# CH32V205V-R0.net
KiCad netlist of a schematic drawn in Altium Designer
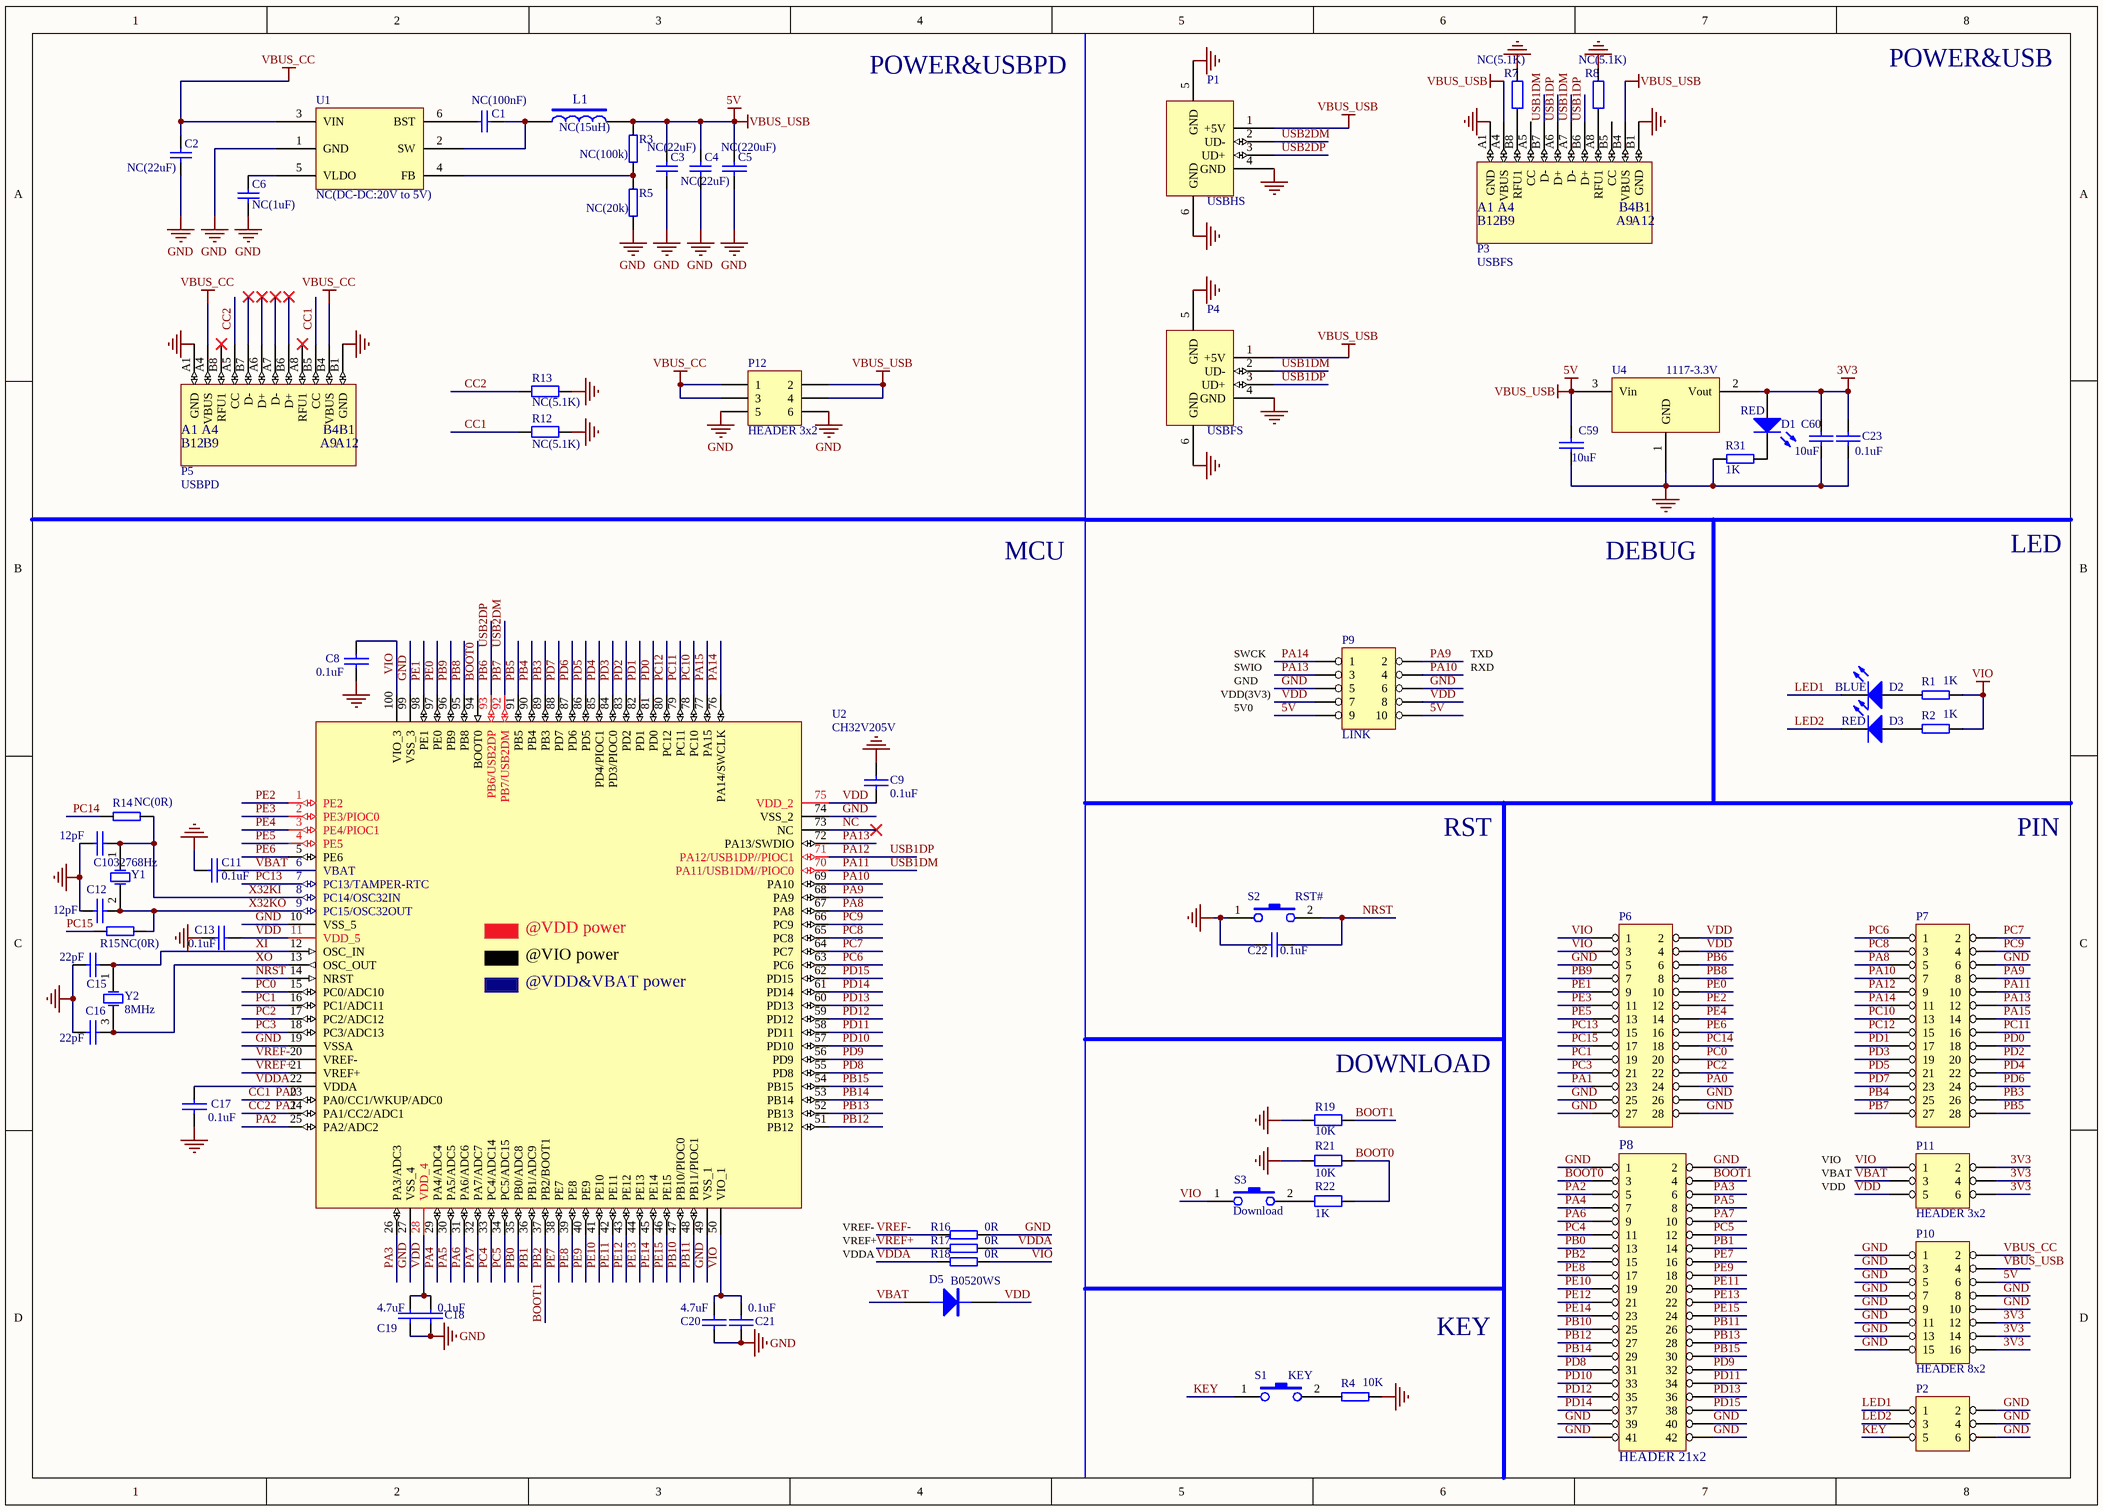
[diagram p0: CH32V205V-R0.SchDoc]

(export (version "E")
  (design (tool "Eeschema 10.0.6"))
  (components
    (comp (ref "C1")
      (value "NC(100nF)")
      (footprint "0402_C")
      (description "贴片电容")
      (libsource (lib "Miscellaneous Devices LC") (part "0603 100nF (104) 10% 50V"))
    )
    (comp (ref "C2")
      (value "NC(22uF)")
      (footprint "0805_C")
      (description "贴片电容")
      (libsource (lib "Miscellaneous Devices LC") (part "0603 100nF (104) 10% 50V"))
    )
    (comp (ref "C3")
      (value "NC(22uF)")
      (footprint "0805_C")
      (description "贴片电容")
      (libsource (lib "Miscellaneous Devices LC") (part "0603 100nF (104) 10% 50V"))
    )
    (comp (ref "C4")
      (value "NC(22uF)")
      (footprint "0805_C")
      (description "贴片电容")
      (libsource (lib "Miscellaneous Devices LC") (part "0603 100nF (104) 10% 50V"))
    )
    (comp (ref "C5")
      (value "NC(220uF)")
      (footprint "CD0.1")
      (description "Capacitor")
      (libsource (lib "") (part "CAP_2"))
    )
    (comp (ref "C6")
      (value "NC(1uF)")
      (footprint "0402_C")
      (description "贴片电容")
      (libsource (lib "Miscellaneous Devices LC") (part "0603 100nF (104) 10% 50V"))
    )
    (comp (ref "C8")
      (value "0.1uF")
      (footprint "0603_C")
      (description "Capacitor")
      (libsource (lib "*") (part "CAP"))
    )
    (comp (ref "C9")
      (value "0.1uF")
      (footprint "0603_C")
      (description "Capacitor")
      (libsource (lib "*") (part "CAP"))
    )
    (comp (ref "C10")
      (value "12pF")
      (footprint "0603_C")
      (description "Capacitor")
      (libsource (lib "*") (part "CAP"))
    )
    (comp (ref "C11")
      (value "0.1uF")
      (footprint "0603_C")
      (description "Capacitor")
      (libsource (lib "*") (part "CAP"))
    )
    (comp (ref "C12")
      (value "12pF")
      (footprint "0603_C")
      (description "Capacitor")
      (libsource (lib "*") (part "CAP"))
    )
    (comp (ref "C13")
      (value "0.1uF")
      (footprint "0603_C")
      (description "Capacitor")
      (libsource (lib "*") (part "CAP"))
    )
    (comp (ref "C15")
      (value "22pF")
      (footprint "0603_C")
      (description "Capacitor")
      (libsource (lib "*") (part "CAP"))
    )
    (comp (ref "C16")
      (value "22pF")
      (footprint "0603_C")
      (description "Capacitor")
      (libsource (lib "*") (part "CAP"))
    )
    (comp (ref "C17")
      (value "0.1uF")
      (footprint "0603_C")
      (description "Capacitor")
      (libsource (lib "*") (part "CAP"))
    )
    (comp (ref "C18")
      (value "0.1uF")
      (footprint "0603_C")
      (description "Capacitor")
      (libsource (lib "*") (part "CAP"))
    )
    (comp (ref "C19")
      (value "4.7uF")
      (footprint "0603_C")
      (description "Capacitor")
      (libsource (lib "*") (part "CAP"))
    )
    (comp (ref "C20")
      (value "4.7uF")
      (footprint "0603_C")
      (description "Capacitor")
      (libsource (lib "*") (part "CAP"))
    )
    (comp (ref "C21")
      (value "0.1uF")
      (footprint "0603_C")
      (description "Capacitor")
      (libsource (lib "*") (part "CAP"))
    )
    (comp (ref "C22")
      (value "0.1uF")
      (footprint "0603_C")
      (description "Capacitor")
      (libsource (lib "") (part "CAP_1"))
    )
    (comp (ref "C23")
      (value "0.1uF")
      (footprint "0402_C")
      (description "Capacitor")
      (libsource (lib "*") (part "CAP"))
    )
    (comp (ref "C59")
      (value "10uF")
      (footprint "0603_C")
      (description "Capacitor")
      (libsource (lib "*") (part "CAP"))
    )
    (comp (ref "C60")
      (value "10uF")
      (footprint "0603_C")
      (description "Capacitor")
      (libsource (lib "*") (part "CAP"))
    )
    (comp (ref "D1")
      (value "RED")
      (footprint "0603+")
      (description "Typical INFRARED GaAs LED")
      (fields (field (name "PUBLISHER") "Altium Limited"))
      (libsource (lib "*") (part "LED0"))
    )
    (comp (ref "D2")
      (value "BLUE")
      (footprint "0603+")
      (description "Typical INFRARED GaAs LED")
      (fields (field (name "PUBLISHER") "Altium Limited"))
      (libsource (lib "*") (part "LED0"))
    )
    (comp (ref "D3")
      (value "RED")
      (footprint "0603+")
      (description "Typical INFRARED GaAs LED")
      (fields (field (name "PUBLISHER") "Altium Limited"))
      (libsource (lib "*") (part "LED0"))
    )
    (comp (ref "D5")
      (value "B0520WS")
      (footprint "SOD-323")
      (description "Diode")
      (libsource (lib "*") (part "DIODE"))
    )
    (comp (ref "L1")
      (value "NC(15uH)")
      (footprint "SMD_6x6mm")
      (libsource (lib "wch_sch_others") (part "INDUCTOR"))
    )
    (comp (ref "P1")
      (value "USBHS")
      (footprint "USBAF")
      (description "USB Port")
      (libsource (lib "*") (part "USB"))
    )
    (comp (ref "P2")
      (value "IO")
      (footprint "MYPCB:IDC6-2.54mm")
      (description "Header, 3-Pin, Dual row")
      (libsource (lib "wch_sch_others") (part "HEADER 3x2"))
    )
    (comp (ref "P3")
      (value "USBFS")
      (footprint "TYPE-C-Receptacle-2.0")
      (libsource (lib "*") (part "TYPE-C1"))
    )
    (comp (ref "P4")
      (value "USBFS")
      (footprint "USBAF")
      (description "USB Port")
      (libsource (lib "*") (part "USB"))
    )
    (comp (ref "P5")
      (value "USBPD")
      (footprint "TYPE-C-Receptacle-2.0")
      (libsource (lib "*") (part "TYPE-C1"))
    )
    (comp (ref "P6")
      (value "~")
      (footprint "MYPCB:IDC28-2.54MM")
      (description "Header, 14-Pin, Dual row")
      (libsource (lib "wch_sch_others") (part "HEADER 14x2"))
    )
    (comp (ref "P7")
      (value "~")
      (footprint "MYPCB:IDC28-2.54MM")
      (description "Header, 14-Pin, Dual row")
      (libsource (lib "wch_sch_others") (part "HEADER 14x2"))
    )
    (comp (ref "P8")
      (value "HEADER 21x2")
      (footprint "MYPCB:IDC42-2.54MM")
      (description "Header, 21-Pin, Dual row")
      (libsource (lib "wch_sch_others") (part "HEADER 21x2"))
    )
    (comp (ref "P9")
      (value "LINK")
      (footprint "MYPCB:IDC10-2.54mm")
      (description "Header, 5-Pin, Dual row")
      (libsource (lib "wch_sch_others") (part "HEADER 5x2"))
    )
    (comp (ref "P10")
      (value "HEADER 8x2")
      (footprint "MYPCB:IDC16-2.54mm")
      (description "Header, 8-Pin, Dual row")
      (libsource (lib "wch_sch_others") (part "HEADER 8x2"))
    )
    (comp (ref "P11")
      (value "HEADER 3x2")
      (footprint "MYPCB:IDC6-2.54mm")
      (description "Header, 3-Pin, Dual row")
      (libsource (lib "wch_sch_others") (part "HEADER 3x2"))
    )
    (comp (ref "P12")
      (value "HEADER 3x2")
      (footprint "MYPCB:IDC6-2.54mm")
      (description "Header, 3-Pin, Dual row")
      (libsource (lib "") (part "HEADER 3x2_1"))
    )
    (comp (ref "R1") (value "1K") (footprint "CHXXX:0603") (libsource (lib "wch_sch_others") (part "RES")))
    (comp (ref "R2") (value "1K") (footprint "CHXXX:0603") (libsource (lib "wch_sch_others") (part "RES")))
    (comp (ref "R3") (value "NC(100k)") (footprint "CHXXX:0603") (libsource (lib "") (part "RES_1")))
    (comp (ref "R4") (value "10K") (footprint "CHXXX:0603") (libsource (lib "wch_sch_others") (part "RES")))
    (comp (ref "R5") (value "NC(20k)") (footprint "CHXXX:0603") (libsource (lib "") (part "RES_1")))
    (comp (ref "R7")
      (value "NC(5.1K)")
      (footprint "0603")
      (description "Resistor")
      (libsource (lib "") (part "Res2_2"))
    )
    (comp (ref "R8")
      (value "NC(5.1K)")
      (footprint "0603")
      (description "Resistor")
      (libsource (lib "") (part "Res2_2"))
    )
    (comp (ref "R12")
      (value "NC(5.1K)")
      (footprint "0402")
      (description "Resistor")
      (libsource (lib "") (part "Res2_1"))
    )
    (comp (ref "R13")
      (value "NC(5.1K)")
      (footprint "0402")
      (description "Resistor")
      (libsource (lib "") (part "Res2_1"))
    )
    (comp (ref "R14")
      (value "NC(0R)")
      (footprint "CHXXX:0603")
      (libsource (lib "wch_sch_others") (part "RES"))
    )
    (comp (ref "R15")
      (value "NC(0R)")
      (footprint "CHXXX:0603")
      (libsource (lib "wch_sch_others") (part "RES"))
    )
    (comp (ref "R16") (value "0R") (footprint "CHXXX:0603") (libsource (lib "*") (part "R")))
    (comp (ref "R17") (value "0R") (footprint "CHXXX:0603") (libsource (lib "*") (part "R")))
    (comp (ref "R18") (value "0R") (footprint "CHXXX:0603") (libsource (lib "*") (part "R")))
    (comp (ref "R19")
      (value "10K")
      (footprint "CHXXX:0603")
      (description "Resistor")
      (fields (field (name "PUBLISHER") "Altium Limited"))
      (libsource (lib "Miscellaneous Devices") (part "Res2"))
    )
    (comp (ref "R21")
      (value "10K")
      (footprint "CHXXX:0603")
      (description "Resistor")
      (fields (field (name "PUBLISHER") "Altium Limited"))
      (libsource (lib "Miscellaneous Devices") (part "Res2"))
    )
    (comp (ref "R22")
      (value "1K")
      (footprint "CHXXX:0603")
      (description "Resistor")
      (fields (field (name "PUBLISHER") "Altium Limited"))
      (libsource (lib "Miscellaneous Devices") (part "Res2"))
    )
    (comp (ref "R31") (value "1K") (footprint "0402") (libsource (lib "wch_sch_others") (part "RES")))
    (comp (ref "S1")
      (value "KEY")
      (footprint "SMD_6.1x3.65x2.5mm-KEY")
      (libsource (lib "wch_sch_others") (part "KEY1"))
    )
    (comp (ref "S2")
      (value "RST#")
      (footprint "SMD_6.1x3.65x2.5mm-KEY")
      (libsource (lib "wch_sch_others") (part "KEY1"))
    )
    (comp (ref "S3")
      (value "Download")
      (footprint "SMD_6.1x3.65x2.5mm-KEY")
      (libsource (lib "wch_sch_others") (part "KEY1"))
    )
    (comp (ref "U1")
      (value "NC(DC-DC:20V to 5V)")
      (footprint "SOT-23-6")
      (description "DCDC")
      (libsource (lib "wch_sch_others") (part "TPS54202"))
    )
    (comp (ref "U2")
      (value "CH32V205V")
      (footprint "LQFP100")
      (description "RISC-V MCU, 192MHz, USB_480M, USB FS, PD, PIOC, ADC, TKEY, 2*OPA, 2*CMP")
      (libsource (lib "CHXXX") (part "CH32V205V"))
    )
    (comp (ref "U4")
      (value "1117-3.3V")
      (footprint "SOT-223")
      (libsource (lib "wch_sch_others") (part "1117-3.3V"))
    )
    (comp (ref "Y1")
      (value "32768Hz")
      (footprint "FC-135")
      (description "Crystal Oscillator")
      (fields (field (name "PUBLISHER") "Altium Limited"))
      (libsource (lib "") (part "XTAL_1"))
    )
    (comp (ref "Y2")
      (value "8MHz")
      (footprint "XT3225")
      (description "Crystal Oscillator")
      (fields (field (name "PUBLISHER") "Altium Limited"))
      (libsource (lib "*") (part "XTAL"))
    )
  )
  (nets
    (net (code "2") (name "/BOOT0") (class "Default")
      (node (ref "P8") (pin "3") (pinfunction "3_3") (pintype "passive"))
      (node (ref "R21") (pin "1") (pinfunction "1_1") (pintype "passive"))
      (node (ref "R22") (pin "1") (pinfunction "1_1") (pintype "passive"))
      (node (ref "U2") (pin "94") (pinfunction "BOOT0_94") (pintype "input"))
    )
    (net (code "3") (name "/BOOT1") (class "Default")
      (node (ref "P8") (pin "15") (pinfunction "15_15") (pintype "passive"))
      (node (ref "P8") (pin "4") (pinfunction "4_4") (pintype "passive"))
      (node (ref "R19") (pin "1") (pinfunction "1_1") (pintype "passive"))
      (node (ref "U2") (pin "37") (pinfunction "PB2/BOOT1_37") (pintype "bidirectional"))
    )
    (net (code "4") (name "/CC1") (class "Default")
      (node (ref "P5") (pin "B5") (pinfunction "CC_B5") (pintype "bidirectional"))
      (node (ref "P6") (pin "24") (pinfunction "24_24") (pintype "passive"))
      (node (ref "R12") (pin "1") (pinfunction "1_1") (pintype "passive"))
      (node (ref "U2") (pin "23") (pinfunction "PA0/CC1/WKUP/ADC0_23") (pintype "bidirectional"))
    )
    (net (code "5") (name "/CC2") (class "Default")
      (node (ref "P5") (pin "A5") (pinfunction "CC_A5") (pintype "bidirectional"))
      (node (ref "P6") (pin "23") (pinfunction "23_23") (pintype "passive"))
      (node (ref "R13") (pin "1") (pinfunction "1_1") (pintype "passive"))
      (node (ref "U2") (pin "24") (pinfunction "PA1/CC2/ADC1_24") (pintype "bidirectional"))
    )
    (net (code "6") (name "/KEY") (class "Default")
      (node (ref "P2") (pin "5") (pinfunction "5_5") (pintype "passive"))
      (node (ref "S1") (pin "1") (pinfunction "1_1") (pintype "passive"))
    )
    (net (code "7") (name "/LED1") (class "Default")
      (node (ref "D2") (pin "2") (pinfunction "K_2") (pintype "passive"))
      (node (ref "P2") (pin "1") (pinfunction "1_1") (pintype "passive"))
    )
    (net (code "8") (name "/LED2") (class "Default")
      (node (ref "D3") (pin "2") (pinfunction "K_2") (pintype "passive"))
      (node (ref "P2") (pin "3") (pinfunction "3_3") (pintype "passive"))
    )
    (net (code "9") (name "/NC") (class "Default")
      (node (ref "U2") (pin "73") (pinfunction "NC_73") (pintype "tri_state+no_connect"))
    )
    (net (code "10") (name "/NRST") (class "Default")
      (node (ref "C22") (pin "2") (pinfunction "2_2") (pintype "passive"))
      (node (ref "S2") (pin "2") (pinfunction "2_2") (pintype "passive"))
      (node (ref "U2") (pin "14") (pinfunction "NRST_14") (pintype "input"))
    )
    (net (code "11") (name "/PA2") (class "Default")
      (node (ref "P8") (pin "5") (pinfunction "5_5") (pintype "passive"))
      (node (ref "U2") (pin "25") (pinfunction "PA2/ADC2_25") (pintype "bidirectional"))
    )
    (net (code "12") (name "/PA3") (class "Default")
      (node (ref "P8") (pin "6") (pinfunction "6_6") (pintype "passive"))
      (node (ref "U2") (pin "26") (pinfunction "PA3/ADC3_26") (pintype "bidirectional"))
    )
    (net (code "13") (name "/PA4") (class "Default")
      (node (ref "P8") (pin "7") (pinfunction "7_7") (pintype "passive"))
      (node (ref "U2") (pin "29") (pinfunction "PA4/ADC4_29") (pintype "bidirectional"))
    )
    (net (code "14") (name "/PA5") (class "Default")
      (node (ref "P8") (pin "8") (pinfunction "8_8") (pintype "passive"))
      (node (ref "U2") (pin "30") (pinfunction "PA5/ADC5_30") (pintype "bidirectional"))
    )
    (net (code "15") (name "/PA6") (class "Default")
      (node (ref "P8") (pin "9") (pinfunction "9_9") (pintype "passive"))
      (node (ref "U2") (pin "31") (pinfunction "PA6/ADC6_31") (pintype "bidirectional"))
    )
    (net (code "16") (name "/PA7") (class "Default")
      (node (ref "P8") (pin "10") (pinfunction "10_10") (pintype "passive"))
      (node (ref "U2") (pin "32") (pinfunction "PA7/ADC7_32") (pintype "bidirectional"))
    )
    (net (code "17") (name "/PA8") (class "Default")
      (node (ref "P7") (pin "5") (pinfunction "5_5") (pintype "passive"))
      (node (ref "U2") (pin "67") (pinfunction "PA8_67") (pintype "bidirectional"))
    )
    (net (code "18") (name "/PA9") (class "Default")
      (node (ref "P7") (pin "8") (pinfunction "8_8") (pintype "passive"))
      (node (ref "P9") (pin "2") (pinfunction "2_2") (pintype "passive"))
      (node (ref "U2") (pin "68") (pinfunction "PA9_68") (pintype "bidirectional"))
    )
    (net (code "19") (name "/PA10") (class "Default")
      (node (ref "P7") (pin "7") (pinfunction "7_7") (pintype "passive"))
      (node (ref "P9") (pin "4") (pinfunction "4_4") (pintype "passive"))
      (node (ref "U2") (pin "69") (pinfunction "PA10_69") (pintype "bidirectional"))
    )
    (net (code "20") (name "/PA11") (class "Default")
      (node (ref "P3") (pin "A7") (pinfunction "D-_A7") (pintype "bidirectional"))
      (node (ref "P3") (pin "B7") (pinfunction "D-_B7") (pintype "bidirectional"))
      (node (ref "P4") (pin "2") (pinfunction "UD-_2") (pintype "bidirectional"))
      (node (ref "P7") (pin "10") (pinfunction "10_10") (pintype "passive"))
      (node (ref "U2") (pin "70") (pinfunction "PA11/USB1DM//PIOC0_70") (pintype "bidirectional"))
    )
    (net (code "21") (name "/PA12") (class "Default")
      (node (ref "P3") (pin "A6") (pinfunction "D+_A6") (pintype "bidirectional"))
      (node (ref "P3") (pin "B6") (pinfunction "D+_B6") (pintype "bidirectional"))
      (node (ref "P4") (pin "3") (pinfunction "UD+_3") (pintype "bidirectional"))
      (node (ref "P7") (pin "9") (pinfunction "9_9") (pintype "passive"))
      (node (ref "U2") (pin "71") (pinfunction "PA12/USB1DP//PIOC1_71") (pintype "bidirectional"))
    )
    (net (code "22") (name "/PA13") (class "Default")
      (node (ref "P7") (pin "12") (pinfunction "12_12") (pintype "passive"))
      (node (ref "P9") (pin "3") (pinfunction "3_3") (pintype "passive"))
      (node (ref "U2") (pin "72") (pinfunction "PA13/SWDIO_72") (pintype "bidirectional"))
    )
    (net (code "23") (name "/PA14") (class "Default")
      (node (ref "P7") (pin "11") (pinfunction "11_11") (pintype "passive"))
      (node (ref "P9") (pin "1") (pinfunction "1_1") (pintype "passive"))
      (node (ref "U2") (pin "76") (pinfunction "PA14/SWCLK_76") (pintype "bidirectional"))
    )
    (net (code "24") (name "/PA15") (class "Default")
      (node (ref "P7") (pin "14") (pinfunction "14_14") (pintype "passive"))
      (node (ref "U2") (pin "77") (pinfunction "PA15_77") (pintype "bidirectional"))
    )
    (net (code "25") (name "/PB0") (class "Default")
      (node (ref "P8") (pin "13") (pinfunction "13_13") (pintype "passive"))
      (node (ref "U2") (pin "35") (pinfunction "PB0/ADC8_35") (pintype "bidirectional"))
    )
    (net (code "26") (name "/PB1") (class "Default")
      (node (ref "P8") (pin "14") (pinfunction "14_14") (pintype "passive"))
      (node (ref "U2") (pin "36") (pinfunction "PB1/ADC9_36") (pintype "bidirectional"))
    )
    (net (code "27") (name "/PB3") (class "Default")
      (node (ref "P7") (pin "26") (pinfunction "26_26") (pintype "passive"))
      (node (ref "U2") (pin "89") (pinfunction "PB3_89") (pintype "bidirectional"))
    )
    (net (code "28") (name "/PB4") (class "Default")
      (node (ref "P7") (pin "25") (pinfunction "25_25") (pintype "passive"))
      (node (ref "U2") (pin "90") (pinfunction "PB4_90") (pintype "bidirectional"))
    )
    (net (code "29") (name "/PB5") (class "Default")
      (node (ref "P7") (pin "28") (pinfunction "28_28") (pintype "passive"))
      (node (ref "U2") (pin "91") (pinfunction "PB5_91") (pintype "bidirectional"))
    )
    (net (code "30") (name "/PB6") (class "Default")
      (node (ref "P1") (pin "3") (pinfunction "UD+_3") (pintype "bidirectional"))
      (node (ref "P6") (pin "6") (pinfunction "6_6") (pintype "passive"))
      (node (ref "U2") (pin "93") (pinfunction "PB6/USB2DP_93") (pintype "bidirectional"))
    )
    (net (code "31") (name "/PB7") (class "Default")
      (node (ref "P1") (pin "2") (pinfunction "UD-_2") (pintype "bidirectional"))
      (node (ref "P7") (pin "27") (pinfunction "27_27") (pintype "passive"))
      (node (ref "U2") (pin "92") (pinfunction "PB7/USB2DM_92") (pintype "bidirectional"))
    )
    (net (code "32") (name "/PB8") (class "Default")
      (node (ref "P6") (pin "8") (pinfunction "8_8") (pintype "passive"))
      (node (ref "U2") (pin "95") (pinfunction "PB8_95") (pintype "bidirectional"))
    )
    (net (code "33") (name "/PB9") (class "Default")
      (node (ref "P6") (pin "7") (pinfunction "7_7") (pintype "passive"))
      (node (ref "U2") (pin "96") (pinfunction "PB9_96") (pintype "bidirectional"))
    )
    (net (code "34") (name "/PB10") (class "Default")
      (node (ref "P8") (pin "25") (pinfunction "25_25") (pintype "passive"))
      (node (ref "U2") (pin "47") (pinfunction "PB10/PIOC0_47") (pintype "bidirectional"))
    )
    (net (code "35") (name "/PB11") (class "Default")
      (node (ref "P8") (pin "26") (pinfunction "26_26") (pintype "passive"))
      (node (ref "U2") (pin "48") (pinfunction "PB11/PIOC1_48") (pintype "bidirectional"))
    )
    (net (code "36") (name "/PB12") (class "Default")
      (node (ref "P8") (pin "27") (pinfunction "27_27") (pintype "passive"))
      (node (ref "U2") (pin "51") (pinfunction "PB12_51") (pintype "bidirectional"))
    )
    (net (code "37") (name "/PB13") (class "Default")
      (node (ref "P8") (pin "28") (pinfunction "28_28") (pintype "passive"))
      (node (ref "U2") (pin "52") (pinfunction "PB13_52") (pintype "bidirectional"))
    )
    (net (code "38") (name "/PB14") (class "Default")
      (node (ref "P8") (pin "29") (pinfunction "29_29") (pintype "passive"))
      (node (ref "U2") (pin "53") (pinfunction "PB14_53") (pintype "bidirectional"))
    )
    (net (code "39") (name "/PB15") (class "Default")
      (node (ref "P8") (pin "30") (pinfunction "30_30") (pintype "passive"))
      (node (ref "U2") (pin "54") (pinfunction "PB15_54") (pintype "bidirectional"))
    )
    (net (code "40") (name "/PC0") (class "Default")
      (node (ref "P6") (pin "20") (pinfunction "20_20") (pintype "passive"))
      (node (ref "U2") (pin "15") (pinfunction "PC0/ADC10_15") (pintype "bidirectional"))
    )
    (net (code "41") (name "/PC1") (class "Default")
      (node (ref "P6") (pin "19") (pinfunction "19_19") (pintype "passive"))
      (node (ref "U2") (pin "16") (pinfunction "PC1/ADC11_16") (pintype "bidirectional"))
    )
    (net (code "42") (name "/PC2") (class "Default")
      (node (ref "P6") (pin "22") (pinfunction "22_22") (pintype "passive"))
      (node (ref "U2") (pin "17") (pinfunction "PC2/ADC12_17") (pintype "bidirectional"))
    )
    (net (code "43") (name "/PC3") (class "Default")
      (node (ref "P6") (pin "21") (pinfunction "21_21") (pintype "passive"))
      (node (ref "U2") (pin "18") (pinfunction "PC3/ADC13_18") (pintype "bidirectional"))
    )
    (net (code "44") (name "/PC4") (class "Default")
      (node (ref "P8") (pin "11") (pinfunction "11_11") (pintype "passive"))
      (node (ref "U2") (pin "33") (pinfunction "PC4/ADC14_33") (pintype "bidirectional"))
    )
    (net (code "45") (name "/PC5") (class "Default")
      (node (ref "P8") (pin "12") (pinfunction "12_12") (pintype "passive"))
      (node (ref "U2") (pin "34") (pinfunction "PC5/ADC15_34") (pintype "bidirectional"))
    )
    (net (code "46") (name "/PC6") (class "Default")
      (node (ref "P7") (pin "1") (pinfunction "1_1") (pintype "passive"))
      (node (ref "U2") (pin "63") (pinfunction "PC6_63") (pintype "bidirectional"))
    )
    (net (code "47") (name "/PC7") (class "Default")
      (node (ref "P7") (pin "2") (pinfunction "2_2") (pintype "passive"))
      (node (ref "U2") (pin "64") (pinfunction "PC7_64") (pintype "bidirectional"))
    )
    (net (code "48") (name "/PC8") (class "Default")
      (node (ref "P7") (pin "3") (pinfunction "3_3") (pintype "passive"))
      (node (ref "U2") (pin "65") (pinfunction "PC8_65") (pintype "bidirectional"))
    )
    (net (code "49") (name "/PC9") (class "Default")
      (node (ref "P7") (pin "4") (pinfunction "4_4") (pintype "passive"))
      (node (ref "U2") (pin "66") (pinfunction "PC9_66") (pintype "bidirectional"))
    )
    (net (code "50") (name "/PC10") (class "Default")
      (node (ref "P7") (pin "13") (pinfunction "13_13") (pintype "passive"))
      (node (ref "U2") (pin "78") (pinfunction "PC10_78") (pintype "bidirectional"))
    )
    (net (code "51") (name "/PC11") (class "Default")
      (node (ref "P7") (pin "16") (pinfunction "16_16") (pintype "passive"))
      (node (ref "U2") (pin "79") (pinfunction "PC11_79") (pintype "bidirectional"))
    )
    (net (code "52") (name "/PC12") (class "Default")
      (node (ref "P7") (pin "15") (pinfunction "15_15") (pintype "passive"))
      (node (ref "U2") (pin "80") (pinfunction "PC12_80") (pintype "bidirectional"))
    )
    (net (code "53") (name "/PC13") (class "Default")
      (node (ref "P6") (pin "15") (pinfunction "15_15") (pintype "passive"))
      (node (ref "U2") (pin "7") (pinfunction "PC13/TAMPER-RTC_7") (pintype "bidirectional"))
    )
    (net (code "54") (name "/PC14") (class "Default")
      (node (ref "P6") (pin "18") (pinfunction "18_18") (pintype "passive"))
      (node (ref "R14") (pin "1") (pintype "passive"))
    )
    (net (code "55") (name "/PC15") (class "Default")
      (node (ref "P6") (pin "17") (pinfunction "17_17") (pintype "passive"))
      (node (ref "R15") (pin "1") (pintype "passive"))
    )
    (net (code "56") (name "/PD0") (class "Default")
      (node (ref "P7") (pin "18") (pinfunction "18_18") (pintype "passive"))
      (node (ref "U2") (pin "81") (pinfunction "PD0_81") (pintype "bidirectional"))
    )
    (net (code "57") (name "/PD1") (class "Default")
      (node (ref "P7") (pin "17") (pinfunction "17_17") (pintype "passive"))
      (node (ref "U2") (pin "82") (pinfunction "PD1_82") (pintype "bidirectional"))
    )
    (net (code "58") (name "/PD2") (class "Default")
      (node (ref "P7") (pin "20") (pinfunction "20_20") (pintype "passive"))
      (node (ref "U2") (pin "83") (pinfunction "PD2_83") (pintype "bidirectional"))
    )
    (net (code "59") (name "/PD3") (class "Default")
      (node (ref "P7") (pin "19") (pinfunction "19_19") (pintype "passive"))
      (node (ref "U2") (pin "84") (pinfunction "PD3/PIOC0_84") (pintype "bidirectional"))
    )
    (net (code "60") (name "/PD4") (class "Default")
      (node (ref "P7") (pin "22") (pinfunction "22_22") (pintype "passive"))
      (node (ref "U2") (pin "85") (pinfunction "PD4/PIOC1_85") (pintype "bidirectional"))
    )
    (net (code "61") (name "/PD5") (class "Default")
      (node (ref "P7") (pin "21") (pinfunction "21_21") (pintype "passive"))
      (node (ref "U2") (pin "86") (pinfunction "PD5_86") (pintype "bidirectional"))
    )
    (net (code "62") (name "/PD6") (class "Default")
      (node (ref "P7") (pin "24") (pinfunction "24_24") (pintype "passive"))
      (node (ref "U2") (pin "87") (pinfunction "PD6_87") (pintype "bidirectional"))
    )
    (net (code "63") (name "/PD7") (class "Default")
      (node (ref "P7") (pin "23") (pinfunction "23_23") (pintype "passive"))
      (node (ref "U2") (pin "88") (pinfunction "PD7_88") (pintype "bidirectional"))
    )
    (net (code "64") (name "/PD8") (class "Default")
      (node (ref "P8") (pin "31") (pinfunction "31_31") (pintype "passive"))
      (node (ref "U2") (pin "55") (pinfunction "PD8_55") (pintype "bidirectional"))
    )
    (net (code "65") (name "/PD9") (class "Default")
      (node (ref "P8") (pin "32") (pinfunction "32_32") (pintype "passive"))
      (node (ref "U2") (pin "56") (pinfunction "PD9_56") (pintype "bidirectional"))
    )
    (net (code "66") (name "/PD10") (class "Default")
      (node (ref "P8") (pin "33") (pinfunction "33_33") (pintype "passive"))
      (node (ref "U2") (pin "57") (pinfunction "PD10_57") (pintype "bidirectional"))
    )
    (net (code "67") (name "/PD11") (class "Default")
      (node (ref "P8") (pin "34") (pinfunction "34_34") (pintype "passive"))
      (node (ref "U2") (pin "58") (pinfunction "PD11_58") (pintype "bidirectional"))
    )
    (net (code "68") (name "/PD12") (class "Default")
      (node (ref "P8") (pin "35") (pinfunction "35_35") (pintype "passive"))
      (node (ref "U2") (pin "59") (pinfunction "PD12_59") (pintype "bidirectional"))
    )
    (net (code "69") (name "/PD13") (class "Default")
      (node (ref "P8") (pin "36") (pinfunction "36_36") (pintype "passive"))
      (node (ref "U2") (pin "60") (pinfunction "PD13_60") (pintype "bidirectional"))
    )
    (net (code "70") (name "/PD14") (class "Default")
      (node (ref "P8") (pin "37") (pinfunction "37_37") (pintype "passive"))
      (node (ref "U2") (pin "61") (pinfunction "PD14_61") (pintype "bidirectional"))
    )
    (net (code "71") (name "/PD15") (class "Default")
      (node (ref "P8") (pin "38") (pinfunction "38_38") (pintype "passive"))
      (node (ref "U2") (pin "62") (pinfunction "PD15_62") (pintype "bidirectional"))
    )
    (net (code "72") (name "/PE0") (class "Default")
      (node (ref "P6") (pin "10") (pinfunction "10_10") (pintype "passive"))
      (node (ref "U2") (pin "97") (pinfunction "PE0_97") (pintype "bidirectional"))
    )
    (net (code "73") (name "/PE1") (class "Default")
      (node (ref "P6") (pin "9") (pinfunction "9_9") (pintype "passive"))
      (node (ref "U2") (pin "98") (pinfunction "PE1_98") (pintype "bidirectional"))
    )
    (net (code "74") (name "/PE2") (class "Default")
      (node (ref "P6") (pin "12") (pinfunction "12_12") (pintype "passive"))
      (node (ref "U2") (pin "1") (pinfunction "PE2_1") (pintype "bidirectional"))
    )
    (net (code "75") (name "/PE3") (class "Default")
      (node (ref "P6") (pin "11") (pinfunction "11_11") (pintype "passive"))
      (node (ref "U2") (pin "2") (pinfunction "PE3/PIOC0_2") (pintype "bidirectional"))
    )
    (net (code "76") (name "/PE4") (class "Default")
      (node (ref "P6") (pin "14") (pinfunction "14_14") (pintype "passive"))
      (node (ref "U2") (pin "3") (pinfunction "PE4/PIOC1_3") (pintype "bidirectional"))
    )
    (net (code "77") (name "/PE5") (class "Default")
      (node (ref "P6") (pin "13") (pinfunction "13_13") (pintype "passive"))
      (node (ref "U2") (pin "4") (pinfunction "PE5_4") (pintype "bidirectional"))
    )
    (net (code "78") (name "/PE6") (class "Default")
      (node (ref "P6") (pin "16") (pinfunction "16_16") (pintype "passive"))
      (node (ref "U2") (pin "5") (pinfunction "PE6_5") (pintype "bidirectional"))
    )
    (net (code "79") (name "/PE7") (class "Default")
      (node (ref "P8") (pin "16") (pinfunction "16_16") (pintype "passive"))
      (node (ref "U2") (pin "38") (pinfunction "PE7_38") (pintype "bidirectional"))
    )
    (net (code "80") (name "/PE8") (class "Default")
      (node (ref "P8") (pin "17") (pinfunction "17_17") (pintype "passive"))
      (node (ref "U2") (pin "39") (pinfunction "PE8_39") (pintype "bidirectional"))
    )
    (net (code "81") (name "/PE9") (class "Default")
      (node (ref "P8") (pin "18") (pinfunction "18_18") (pintype "passive"))
      (node (ref "U2") (pin "40") (pinfunction "PE9_40") (pintype "bidirectional"))
    )
    (net (code "82") (name "/PE10") (class "Default")
      (node (ref "P8") (pin "19") (pinfunction "19_19") (pintype "passive"))
      (node (ref "U2") (pin "41") (pinfunction "PE10_41") (pintype "bidirectional"))
    )
    (net (code "83") (name "/PE11") (class "Default")
      (node (ref "P8") (pin "20") (pinfunction "20_20") (pintype "passive"))
      (node (ref "U2") (pin "42") (pinfunction "PE11_42") (pintype "bidirectional"))
    )
    (net (code "84") (name "/PE12") (class "Default")
      (node (ref "P8") (pin "21") (pinfunction "21_21") (pintype "passive"))
      (node (ref "U2") (pin "43") (pinfunction "PE12_43") (pintype "bidirectional"))
    )
    (net (code "85") (name "/PE13") (class "Default")
      (node (ref "P8") (pin "22") (pinfunction "22_22") (pintype "passive"))
      (node (ref "U2") (pin "44") (pinfunction "PE13_44") (pintype "bidirectional"))
    )
    (net (code "86") (name "/PE14") (class "Default")
      (node (ref "P8") (pin "23") (pinfunction "23_23") (pintype "passive"))
      (node (ref "U2") (pin "45") (pinfunction "PE14_45") (pintype "bidirectional"))
    )
    (net (code "87") (name "/PE15") (class "Default")
      (node (ref "P8") (pin "24") (pinfunction "24_24") (pintype "passive"))
      (node (ref "U2") (pin "46") (pinfunction "PE15_46") (pintype "bidirectional"))
    )
    (net (code "88") (name "/VBAT") (class "Default")
      (node (ref "C11") (pin "2") (pinfunction "2_2") (pintype "passive"))
      (node (ref "D5") (pin "1") (pinfunction "A_1") (pintype "passive"))
      (node (ref "P11") (pin "3") (pinfunction "3_3") (pintype "passive"))
      (node (ref "U2") (pin "6") (pinfunction "VBAT_6") (pintype "power_in"))
    )
    (net (code "89") (name "/VDD") (class "Default")
      (node (ref "C13") (pin "1") (pinfunction "1_1") (pintype "passive"))
      (node (ref "C18") (pin "2") (pinfunction "2_2") (pintype "passive"))
      (node (ref "C19") (pin "1") (pinfunction "1_1") (pintype "passive"))
      (node (ref "C9") (pin "1") (pinfunction "1_1") (pintype "passive"))
      (node (ref "D5") (pin "2") (pinfunction "K_2") (pintype "passive"))
      (node (ref "P11") (pin "5") (pinfunction "5_5") (pintype "passive"))
      (node (ref "P6") (pin "2") (pinfunction "2_2") (pintype "passive"))
      (node (ref "P6") (pin "4") (pinfunction "4_4") (pintype "passive"))
      (node (ref "P9") (pin "7") (pinfunction "7_7") (pintype "passive"))
      (node (ref "P9") (pin "8") (pinfunction "8_8") (pintype "passive"))
      (node (ref "U2") (pin "11") (pinfunction "VDD_5_11") (pintype "power_in"))
      (node (ref "U2") (pin "28") (pinfunction "VDD_4_28") (pintype "power_in"))
      (node (ref "U2") (pin "75") (pinfunction "VDD_2_75") (pintype "power_in"))
    )
    (net (code "90") (name "/VDDA") (class "Default")
      (node (ref "C17") (pin "1") (pinfunction "1_1") (pintype "passive"))
      (node (ref "R17") (pin "1") (pinfunction "1_1") (pintype "passive"))
      (node (ref "R18") (pin "2") (pinfunction "2_2") (pintype "passive"))
      (node (ref "U2") (pin "22") (pinfunction "VDDA_22") (pintype "power_in"))
    )
    (net (code "91") (name "/VREF+") (class "Default")
      (node (ref "R17") (pin "2") (pinfunction "2_2") (pintype "passive"))
      (node (ref "U2") (pin "21") (pinfunction "VREF+_21") (pintype "power_in"))
    )
    (net (code "92") (name "/VREF-") (class "Default")
      (node (ref "R16") (pin "2") (pinfunction "2_2") (pintype "passive"))
      (node (ref "U2") (pin "20") (pinfunction "VREF-_20") (pintype "power_in"))
    )
    (net (code "93") (name "/X32KI") (class "Default")
      (node (ref "C10") (pin "2") (pinfunction "2_2") (pintype "passive"))
      (node (ref "R14") (pin "2") (pintype "passive"))
      (node (ref "U2") (pin "8") (pinfunction "PC14/OSC32IN_8") (pintype "bidirectional"))
      (node (ref "Y1") (pin "1") (pinfunction "OSC1_1") (pintype "passive"))
    )
    (net (code "94") (name "/X32KO") (class "Default")
      (node (ref "C12") (pin "2") (pinfunction "2_2") (pintype "passive"))
      (node (ref "R15") (pin "2") (pintype "passive"))
      (node (ref "U2") (pin "9") (pinfunction "PC15/OSC32OUT_9") (pintype "bidirectional"))
      (node (ref "Y1") (pin "2") (pinfunction "OSC2_2") (pintype "passive"))
    )
    (net (code "95") (name "/XI") (class "Default")
      (node (ref "C15") (pin "2") (pinfunction "2_2") (pintype "passive"))
      (node (ref "U2") (pin "12") (pinfunction "OSC_IN_12") (pintype "input"))
      (node (ref "Y2") (pin "1") (pinfunction "OSC1_1") (pintype "passive"))
    )
    (net (code "96") (name "/XO") (class "Default")
      (node (ref "C16") (pin "2") (pinfunction "2_2") (pintype "passive"))
      (node (ref "U2") (pin "13") (pinfunction "OSC_OUT_13") (pintype "output"))
      (node (ref "Y2") (pin "3") (pinfunction "OSC2_3") (pintype "passive"))
    )
    (net (code "97") (name "3V3") (class "Default")
      (node (ref "C23") (pin "1") (pinfunction "1_1") (pintype "passive"))
      (node (ref "C60") (pin "1") (pinfunction "1_1") (pintype "passive"))
      (node (ref "D1") (pin "1") (pinfunction "A_1") (pintype "passive"))
      (node (ref "P10") (pin "12") (pinfunction "12_12") (pintype "passive"))
      (node (ref "P10") (pin "14") (pinfunction "14_14") (pintype "passive"))
      (node (ref "P10") (pin "16") (pinfunction "16_16") (pintype "passive"))
      (node (ref "P11") (pin "2") (pinfunction "2_2") (pintype "passive"))
      (node (ref "P11") (pin "4") (pinfunction "4_4") (pintype "passive"))
      (node (ref "P11") (pin "6") (pinfunction "6_6") (pintype "passive"))
      (node (ref "U4") (pin "2") (pinfunction "Vout_2") (pintype "passive"))
    )
    (net (code "98") (name "5V") (class "Default")
      (node (ref "C3") (pin "2") (pinfunction "2_2") (pintype "passive"))
      (node (ref "C4") (pin "2") (pinfunction "2_2") (pintype "passive"))
      (node (ref "C5") (pin "1") (pinfunction "1_1") (pintype "passive"))
      (node (ref "C59") (pin "1") (pinfunction "1_1") (pintype "passive"))
      (node (ref "L1") (pin "2") (pinfunction "2_2") (pintype "passive"))
      (node (ref "P1") (pin "1") (pinfunction "+5V_1") (pintype "power_in"))
      (node (ref "P10") (pin "4") (pinfunction "4_4") (pintype "passive"))
      (node (ref "P10") (pin "6") (pinfunction "6_6") (pintype "passive"))
      (node (ref "P12") (pin "2") (pinfunction "2_2") (pintype "passive"))
      (node (ref "P12") (pin "4") (pinfunction "4_4") (pintype "passive"))
      (node (ref "P3") (pin "A4") (pinfunction "VBUS_A4") (pintype "bidirectional"))
      (node (ref "P3") (pin "B4") (pinfunction "VBUS_B4") (pintype "bidirectional"))
      (node (ref "P4") (pin "1") (pinfunction "+5V_1") (pintype "power_in"))
      (node (ref "P9") (pin "10") (pinfunction "10_10") (pintype "passive"))
      (node (ref "P9") (pin "9") (pinfunction "9_9") (pintype "passive"))
      (node (ref "R3") (pin "2") (pintype "passive"))
      (node (ref "U4") (pin "3") (pinfunction "Vin_3") (pintype "passive"))
    )
    (net (code "99") (name "GND") (class "Default")
      (node (ref "C10") (pin "1") (pinfunction "1_1") (pintype "passive"))
      (node (ref "C11") (pin "1") (pinfunction "1_1") (pintype "passive"))
      (node (ref "C12") (pin "1") (pinfunction "1_1") (pintype "passive"))
      (node (ref "C13") (pin "2") (pinfunction "2_2") (pintype "passive"))
      (node (ref "C15") (pin "1") (pinfunction "1_1") (pintype "passive"))
      (node (ref "C16") (pin "1") (pinfunction "1_1") (pintype "passive"))
      (node (ref "C17") (pin "2") (pinfunction "2_2") (pintype "passive"))
      (node (ref "C18") (pin "1") (pinfunction "1_1") (pintype "passive"))
      (node (ref "C19") (pin "2") (pinfunction "2_2") (pintype "passive"))
      (node (ref "C2") (pin "1") (pinfunction "1_1") (pintype "passive"))
      (node (ref "C20") (pin "2") (pinfunction "2_2") (pintype "passive"))
      (node (ref "C21") (pin "2") (pinfunction "2_2") (pintype "passive"))
      (node (ref "C22") (pin "1") (pinfunction "1_1") (pintype "passive"))
      (node (ref "C23") (pin "2") (pinfunction "2_2") (pintype "passive"))
      (node (ref "C3") (pin "1") (pinfunction "1_1") (pintype "passive"))
      (node (ref "C4") (pin "1") (pinfunction "1_1") (pintype "passive"))
      (node (ref "C5") (pin "2") (pinfunction "2_2") (pintype "passive"))
      (node (ref "C59") (pin "2") (pinfunction "2_2") (pintype "passive"))
      (node (ref "C6") (pin "1") (pinfunction "1_1") (pintype "passive"))
      (node (ref "C60") (pin "2") (pinfunction "2_2") (pintype "passive"))
      (node (ref "C8") (pin "1") (pinfunction "1_1") (pintype "passive"))
      (node (ref "C9") (pin "2") (pinfunction "2_2") (pintype "passive"))
      (node (ref "P1") (pin "4") (pinfunction "GND_4") (pintype "power_in"))
      (node (ref "P1") (pin "5") (pinfunction "GND_5") (pintype "power_in"))
      (node (ref "P1") (pin "6") (pinfunction "GND_6") (pintype "power_in"))
      (node (ref "P10") (pin "1") (pinfunction "1_1") (pintype "passive"))
      (node (ref "P10") (pin "10") (pinfunction "10_10") (pintype "passive"))
      (node (ref "P10") (pin "11") (pinfunction "11_11") (pintype "passive"))
      (node (ref "P10") (pin "13") (pinfunction "13_13") (pintype "passive"))
      (node (ref "P10") (pin "15") (pinfunction "15_15") (pintype "passive"))
      (node (ref "P10") (pin "3") (pinfunction "3_3") (pintype "passive"))
      (node (ref "P10") (pin "5") (pinfunction "5_5") (pintype "passive"))
      (node (ref "P10") (pin "7") (pinfunction "7_7") (pintype "passive"))
      (node (ref "P10") (pin "8") (pinfunction "8_8") (pintype "passive"))
      (node (ref "P10") (pin "9") (pinfunction "9_9") (pintype "passive"))
      (node (ref "P12") (pin "5") (pinfunction "5_5") (pintype "passive"))
      (node (ref "P12") (pin "6") (pinfunction "6_6") (pintype "passive"))
      (node (ref "P2") (pin "2") (pinfunction "2_2") (pintype "passive"))
      (node (ref "P2") (pin "4") (pinfunction "4_4") (pintype "passive"))
      (node (ref "P2") (pin "6") (pinfunction "6_6") (pintype "passive"))
      (node (ref "P3") (pin "A1") (pinfunction "GND_A1") (pintype "bidirectional"))
      (node (ref "P3") (pin "B1") (pinfunction "GND_B1") (pintype "bidirectional"))
      (node (ref "P4") (pin "4") (pinfunction "GND_4") (pintype "power_in"))
      (node (ref "P4") (pin "5") (pinfunction "GND_5") (pintype "power_in"))
      (node (ref "P4") (pin "6") (pinfunction "GND_6") (pintype "power_in"))
      (node (ref "P5") (pin "A1") (pinfunction "GND_A1") (pintype "bidirectional"))
      (node (ref "P5") (pin "B1") (pinfunction "GND_B1") (pintype "bidirectional"))
      (node (ref "P6") (pin "25") (pinfunction "25_25") (pintype "passive"))
      (node (ref "P6") (pin "26") (pinfunction "26_26") (pintype "passive"))
      (node (ref "P6") (pin "27") (pinfunction "27_27") (pintype "passive"))
      (node (ref "P6") (pin "28") (pinfunction "28_28") (pintype "passive"))
      (node (ref "P6") (pin "5") (pinfunction "5_5") (pintype "passive"))
      (node (ref "P7") (pin "6") (pinfunction "6_6") (pintype "passive"))
      (node (ref "P8") (pin "1") (pinfunction "1_1") (pintype "passive"))
      (node (ref "P8") (pin "2") (pinfunction "2_2") (pintype "passive"))
      (node (ref "P8") (pin "39") (pinfunction "39_39") (pintype "passive"))
      (node (ref "P8") (pin "40") (pinfunction "40_40") (pintype "passive"))
      (node (ref "P8") (pin "41") (pinfunction "41_41") (pintype "passive"))
      (node (ref "P8") (pin "42") (pinfunction "42_42") (pintype "passive"))
      (node (ref "P9") (pin "5") (pinfunction "5_5") (pintype "passive"))
      (node (ref "P9") (pin "6") (pinfunction "6_6") (pintype "passive"))
      (node (ref "R12") (pin "2") (pinfunction "2_2") (pintype "passive"))
      (node (ref "R13") (pin "2") (pinfunction "2_2") (pintype "passive"))
      (node (ref "R16") (pin "1") (pinfunction "1_1") (pintype "passive"))
      (node (ref "R19") (pin "2") (pinfunction "2_2") (pintype "passive"))
      (node (ref "R21") (pin "2") (pinfunction "2_2") (pintype "passive"))
      (node (ref "R31") (pin "1") (pintype "passive"))
      (node (ref "R4") (pin "1") (pintype "passive"))
      (node (ref "R5") (pin "1") (pintype "passive"))
      (node (ref "R7") (pin "2") (pinfunction "2_2") (pintype "passive"))
      (node (ref "R8") (pin "2") (pinfunction "2_2") (pintype "passive"))
      (node (ref "S2") (pin "1") (pinfunction "1_1") (pintype "passive"))
      (node (ref "U1") (pin "1") (pinfunction "GND_1") (pintype "passive"))
      (node (ref "U2") (pin "10") (pinfunction "VSS_5_10") (pintype "power_in"))
      (node (ref "U2") (pin "19") (pinfunction "VSSA_19") (pintype "power_in"))
      (node (ref "U2") (pin "27") (pinfunction "VSS_4_27") (pintype "power_in"))
      (node (ref "U2") (pin "49") (pinfunction "VSS_1_49") (pintype "power_in"))
      (node (ref "U2") (pin "74") (pinfunction "VSS_2_74") (pintype "power_in"))
      (node (ref "U2") (pin "99") (pinfunction "VSS_3_99") (pintype "power_in"))
      (node (ref "U4") (pin "1") (pinfunction "GND_1") (pintype "passive"))
    )
    (net (code "100") (name "Net-(D1-K)") (class "Default")
      (node (ref "D1") (pin "2") (pinfunction "K_2") (pintype "passive"))
      (node (ref "R31") (pin "2") (pintype "passive"))
    )
    (net (code "101") (name "Net-(D2-A)") (class "Default")
      (node (ref "D2") (pin "1") (pinfunction "A_1") (pintype "passive"))
      (node (ref "R1") (pin "2") (pintype "passive"))
    )
    (net (code "102") (name "Net-(D3-A)") (class "Default")
      (node (ref "D3") (pin "1") (pinfunction "A_1") (pintype "passive"))
      (node (ref "R2") (pin "2") (pintype "passive"))
    )
    (net (code "103") (name "Net-(P3-RFU1-PadA8)") (class "Default")
      (node (ref "P3") (pin "A8") (pinfunction "RFU1_A8") (pintype "bidirectional"))
      (node (ref "R8") (pin "1") (pinfunction "1_1") (pintype "passive"))
    )
    (net (code "104") (name "Net-(P3-RFU1-PadB8)") (class "Default")
      (node (ref "P3") (pin "B8") (pinfunction "RFU1_B8") (pintype "bidirectional"))
      (node (ref "R7") (pin "1") (pinfunction "1_1") (pintype "passive"))
    )
    (net (code "105") (name "Net-(R4-Pad2)") (class "Default")
      (node (ref "R4") (pin "2") (pintype "passive"))
      (node (ref "S1") (pin "2") (pinfunction "2_2") (pintype "passive"))
    )
    (net (code "106") (name "Net-(R22-Pad2)") (class "Default")
      (node (ref "R22") (pin "2") (pinfunction "2_2") (pintype "passive"))
      (node (ref "S3") (pin "2") (pinfunction "2_2") (pintype "passive"))
    )
    (net (code "107") (name "Net-(U1-BST)") (class "Default")
      (node (ref "C1") (pin "2") (pinfunction "2_2") (pintype "passive"))
      (node (ref "U1") (pin "6") (pinfunction "BST_6") (pintype "passive"))
    )
    (net (code "108") (name "Net-(U1-FB)") (class "Default")
      (node (ref "R3") (pin "1") (pintype "passive"))
      (node (ref "R5") (pin "2") (pintype "passive"))
      (node (ref "U1") (pin "4") (pinfunction "FB_4") (pintype "passive"))
    )
    (net (code "109") (name "Net-(U1-SW)") (class "Default")
      (node (ref "C1") (pin "1") (pinfunction "1_1") (pintype "passive"))
      (node (ref "L1") (pin "1") (pinfunction "1_1") (pintype "passive"))
      (node (ref "U1") (pin "2") (pinfunction "SW_2") (pintype "passive"))
    )
    (net (code "110") (name "Net-(U1-VLDO)") (class "Default")
      (node (ref "C6") (pin "2") (pinfunction "2_2") (pintype "passive"))
      (node (ref "U1") (pin "5") (pinfunction "VLDO_5") (pintype "passive"))
    )
    (net (code "111") (name "VBUS_CC") (class "Default")
      (node (ref "C2") (pin "2") (pinfunction "2_2") (pintype "passive"))
      (node (ref "P10") (pin "2") (pinfunction "2_2") (pintype "passive"))
      (node (ref "P12") (pin "1") (pinfunction "1_1") (pintype "passive"))
      (node (ref "P12") (pin "3") (pinfunction "3_3") (pintype "passive"))
      (node (ref "P5") (pin "A4") (pinfunction "VBUS_A4") (pintype "bidirectional"))
      (node (ref "P5") (pin "B4") (pinfunction "VBUS_B4") (pintype "bidirectional"))
      (node (ref "U1") (pin "3") (pinfunction "VIN_3") (pintype "passive"))
    )
    (net (code "112") (name "VIO") (class "Default")
      (node (ref "C20") (pin "1") (pinfunction "1_1") (pintype "passive"))
      (node (ref "C21") (pin "1") (pinfunction "1_1") (pintype "passive"))
      (node (ref "C8") (pin "2") (pinfunction "2_2") (pintype "passive"))
      (node (ref "P11") (pin "1") (pinfunction "1_1") (pintype "passive"))
      (node (ref "P6") (pin "1") (pinfunction "1_1") (pintype "passive"))
      (node (ref "P6") (pin "3") (pinfunction "3_3") (pintype "passive"))
      (node (ref "R1") (pin "1") (pintype "passive"))
      (node (ref "R18") (pin "1") (pinfunction "1_1") (pintype "passive"))
      (node (ref "R2") (pin "1") (pintype "passive"))
      (node (ref "S3") (pin "1") (pinfunction "1_1") (pintype "passive"))
      (node (ref "U2") (pin "100") (pinfunction "VIO_3_100") (pintype "power_in"))
      (node (ref "U2") (pin "50") (pinfunction "VIO_1_50") (pintype "power_in"))
    )
    (net (code "113") (name "unconnected-(P3-CC-PadA5)") (class "Default")
      (node (ref "P3") (pin "A5") (pinfunction "CC_A5") (pintype "bidirectional"))
    )
    (net (code "114") (name "unconnected-(P3-CC-PadB5)") (class "Default")
      (node (ref "P3") (pin "B5") (pinfunction "CC_B5") (pintype "bidirectional"))
    )
    (net (code "115") (name "unconnected-(P5-D+-PadA6)") (class "Default")
      (node (ref "P5") (pin "A6") (pinfunction "D+_A6") (pintype "bidirectional+no_connect"))
    )
    (net (code "116") (name "unconnected-(P5-D+-PadB6)") (class "Default")
      (node (ref "P5") (pin "B6") (pinfunction "D+_B6") (pintype "bidirectional+no_connect"))
    )
    (net (code "117") (name "unconnected-(P5-D--PadA7)") (class "Default")
      (node (ref "P5") (pin "A7") (pinfunction "D-_A7") (pintype "bidirectional+no_connect"))
    )
    (net (code "118") (name "unconnected-(P5-D--PadB7)") (class "Default")
      (node (ref "P5") (pin "B7") (pinfunction "D-_B7") (pintype "bidirectional+no_connect"))
    )
    (net (code "119") (name "unconnected-(P5-RFU1-PadA8)") (class "Default")
      (node (ref "P5") (pin "A8") (pinfunction "RFU1_A8") (pintype "bidirectional+no_connect"))
    )
    (net (code "120") (name "unconnected-(P5-RFU1-PadB8)") (class "Default")
      (node (ref "P5") (pin "B8") (pinfunction "RFU1_B8") (pintype "bidirectional+no_connect"))
    )
  )
)
